# TS100C.net
KiCad netlist of a schematic drawn in Altium Designer
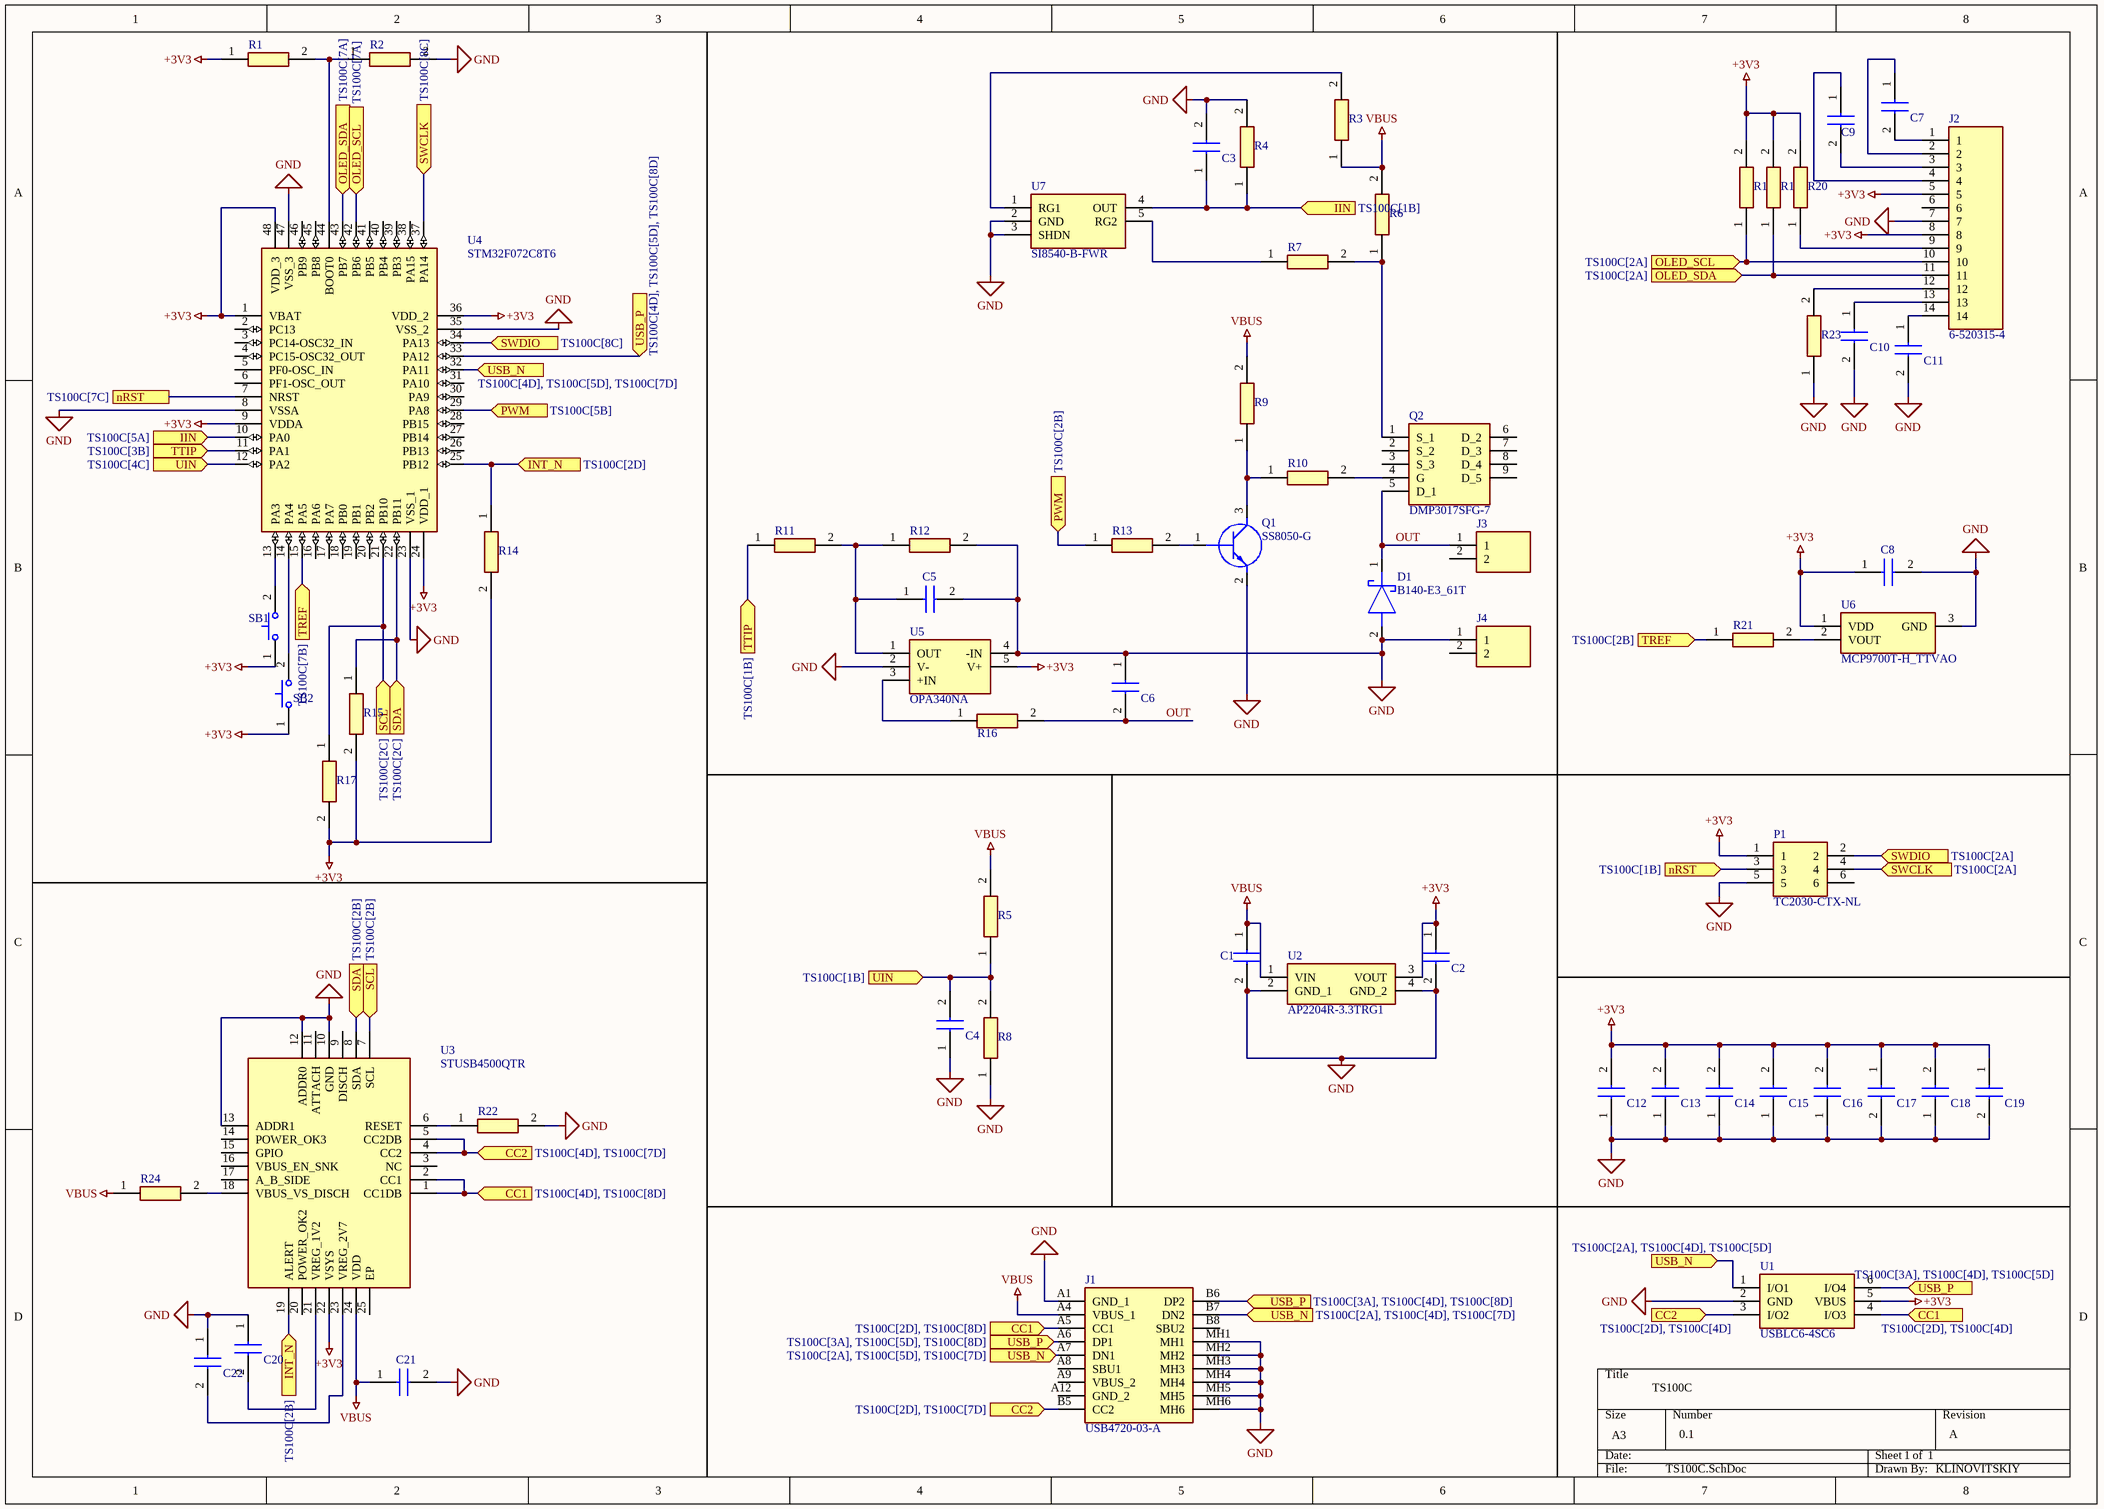
[diagram p0: TS100C.SchDoc]

(export (version "E")
  (design (tool "Eeschema 10.0.6"))
  (components
    (comp (ref "C1")
      (value "MAJCT168BB7105KTEA01")
      (footprint "SamacSys:MAJx16")
      (description "Capacitor")
      (libsource (lib "*") (part "MAJCT168BB7105KTEA01"))
    )
    (comp (ref "C2")
      (value "MAJCT168BB7105KTEA01")
      (footprint "SamacSys:MAJx16")
      (description "Capacitor")
      (libsource (lib "*") (part "MAJCT168BB7105KTEA01"))
    )
    (comp (ref "C3")
      (value "MAASU21GSB7104MTCA01")
      (footprint "SamacSys:CAPC2012X135N")
      (description "Capacitor")
      (fields (field (name "MOUSER PART NUMBER") "963-MAASU21GSB7104M"))
      (libsource (lib "*") (part "MAASU21GSB7104MTCA01"))
    )
    (comp (ref "C4")
      (value "MAASU21GSB7104MTCA01")
      (footprint "SamacSys:CAPC2012X135N")
      (description "Capacitor")
      (fields (field (name "MOUSER PART NUMBER") "963-MAASU21GSB7104M"))
      (libsource (lib "*") (part "MAASU21GSB7104MTCA01"))
    )
    (comp (ref "C5")
      (value "C0805C180JAGACTU")
      (footprint "SamacSys:C0805")
      (description "Capacitor")
      (fields (field (name "MOUSER PART NUMBER") "80-C0805C180JAGACTU"))
      (libsource (lib "*") (part "C0805C180JAGACTU"))
    )
    (comp (ref "C6")
      (value "C0805C180JAGACTU")
      (footprint "SamacSys:C0805")
      (description "Capacitor")
      (fields (field (name "MOUSER PART NUMBER") "80-C0805C180JAGACTU"))
      (libsource (lib "*") (part "C0805C180JAGACTU"))
    )
    (comp (ref "C7")
      (value "MAJCT168BB7105KTEA01")
      (footprint "SamacSys:MAJx16")
      (description "Capacitor")
      (libsource (lib "*") (part "MAJCT168BB7105KTEA01"))
    )
    (comp (ref "C8")
      (value "MAASU21GSB7104MTCA01")
      (footprint "SamacSys:CAPC2012X135N")
      (description "Capacitor")
      (fields (field (name "MOUSER PART NUMBER") "963-MAASU21GSB7104M"))
      (libsource (lib "*") (part "MAASU21GSB7104MTCA01"))
    )
    (comp (ref "C9")
      (value "MAJCT168BB7105KTEA01")
      (footprint "SamacSys:MAJx16")
      (description "Capacitor")
      (libsource (lib "*") (part "MAJCT168BB7105KTEA01"))
    )
    (comp (ref "C10")
      (value "MAJCT168BB7105KTEA01")
      (footprint "SamacSys:MAJx16")
      (description "Capacitor")
      (libsource (lib "*") (part "MAJCT168BB7105KTEA01"))
    )
    (comp (ref "C11")
      (value "MAJCT168BB7105KTEA01")
      (footprint "SamacSys:MAJx16")
      (description "Capacitor")
      (libsource (lib "*") (part "MAJCT168BB7105KTEA01"))
    )
    (comp (ref "C12")
      (value "MAASU21GSB7104MTCA01")
      (footprint "SamacSys:CAPC2012X135N")
      (description "Capacitor")
      (fields (field (name "MOUSER PART NUMBER") "963-MAASU21GSB7104M"))
      (libsource (lib "*") (part "MAASU21GSB7104MTCA01"))
    )
    (comp (ref "C13")
      (value "MAASU21GSB7104MTCA01")
      (footprint "SamacSys:CAPC2012X135N")
      (description "Capacitor")
      (fields (field (name "MOUSER PART NUMBER") "963-MAASU21GSB7104M"))
      (libsource (lib "*") (part "MAASU21GSB7104MTCA01"))
    )
    (comp (ref "C14")
      (value "MAASU21GSB7104MTCA01")
      (footprint "SamacSys:CAPC2012X135N")
      (description "Capacitor")
      (fields (field (name "MOUSER PART NUMBER") "963-MAASU21GSB7104M"))
      (libsource (lib "*") (part "MAASU21GSB7104MTCA01"))
    )
    (comp (ref "C15")
      (value "MAASU21GSB7104MTCA01")
      (footprint "SamacSys:CAPC2012X135N")
      (description "Capacitor")
      (fields (field (name "MOUSER PART NUMBER") "963-MAASU21GSB7104M"))
      (libsource (lib "*") (part "MAASU21GSB7104MTCA01"))
    )
    (comp (ref "C16")
      (value "MAASU21GSB7104MTCA01")
      (footprint "SamacSys:CAPC2012X135N")
      (description "Capacitor")
      (fields (field (name "MOUSER PART NUMBER") "963-MAASU21GSB7104M"))
      (libsource (lib "*") (part "MAASU21GSB7104MTCA01"))
    )
    (comp (ref "C17")
      (value "MAJCT168BB7105KTEA01")
      (footprint "SamacSys:MAJx16")
      (description "Capacitor")
      (libsource (lib "*") (part "MAJCT168BB7105KTEA01"))
    )
    (comp (ref "C18")
      (value "MAASU21GSB7104MTCA01")
      (footprint "SamacSys:CAPC2012X135N")
      (description "Capacitor")
      (fields (field (name "MOUSER PART NUMBER") "963-MAASU21GSB7104M"))
      (libsource (lib "*") (part "MAASU21GSB7104MTCA01"))
    )
    (comp (ref "C19")
      (value "MAJCT168BB7105KTEA01")
      (footprint "SamacSys:MAJx16")
      (description "Capacitor")
      (libsource (lib "*") (part "MAJCT168BB7105KTEA01"))
    )
    (comp (ref "C20")
      (value "MAJCT168BB7105KTEA01")
      (footprint "SamacSys:MAJx16")
      (description "Capacitor")
      (libsource (lib "*") (part "MAJCT168BB7105KTEA01"))
    )
    (comp (ref "C21")
      (value "MAASU21GSB7104MTCA01")
      (footprint "SamacSys:CAPC2012X135N")
      (description "Capacitor")
      (fields (field (name "MOUSER PART NUMBER") "963-MAASU21GSB7104M"))
      (libsource (lib "*") (part "MAASU21GSB7104MTCA01"))
    )
    (comp (ref "C22")
      (value "MAJCT168BB7105KTEA01")
      (footprint "SamacSys:MAJx16")
      (description "Capacitor")
      (libsource (lib "*") (part "MAJCT168BB7105KTEA01"))
    )
    (comp (ref "D1")
      (value "B140-E3_61T")
      (footprint "SamacSys:DIOM5127X229N")
      (description "Schottky Diode")
      (fields
        (field (name "MANUFACTURER_PART_NUMBER") "B140-E3/61T")
        (field (name "MOUSER PART NUMBER") "625-B140-E3/61T")
      )
      (libsource (lib "*") (part "B140-E3_61T"))
    )
    (comp (ref "J1")
      (value "USB4720-03-A")
      (footprint "SamacSys:USB472003A")
      (description "Connector")
      (fields (field (name "MOUSER PART NUMBER") "640-USB472003A"))
      (libsource (lib "*") (part "USB4720-03-A"))
    )
    (comp (ref "J2")
      (value "6-520315-4")
      (footprint "SamacSys:65203154")
      (description "Connector")
      (fields (field (name "MOUSER PART NUMBER") "571-6-520315-4"))
      (libsource (lib "*") (part "6-520315-4"))
    )
    (comp (ref "J3")
      (value "1-770166-0")
      (footprint "SamacSys:17701660")
      (description "Connector")
      (fields (field (name "MOUSER PART NUMBER") "571-1-770166-0"))
      (libsource (lib "*") (part "1-770166-0"))
    )
    (comp (ref "J4")
      (value "1-770166-0")
      (footprint "SamacSys:17701660")
      (description "Connector")
      (fields (field (name "MOUSER PART NUMBER") "571-1-770166-0"))
      (libsource (lib "*") (part "1-770166-0"))
    )
    (comp (ref "P1")
      (value "TC2030-CTX-NL")
      (footprint "SamacSys:TC2030MCPNL10")
      (description "Connector")
      (libsource (lib "*") (part "TC2030-CTX-NL"))
    )
    (comp (ref "Q1")
      (value "SS8050-G")
      (footprint "SamacSys:SOT95P240X115-3N")
      (description "Transistor BJT NPN")
      (fields (field (name "MOUSER PART NUMBER") "750-SS8050-G"))
      (libsource (lib "*") (part "SS8050-G"))
    )
    (comp (ref "Q2")
      (value "DMP3017SFG-7")
      (footprint "SamacSys:DMP3007SFG7")
      (description "MOSFET (P-Channel)")
      (fields (field (name "MOUSER PART NUMBER") "621-DMP3017SFG-7"))
      (libsource (lib "*") (part "DMP3017SFG-7"))
    )
    (comp (ref "R1")
      (value "WSL080500000ZEA9")
      (footprint "SamacSys:RESC2013X84N")
      (description "Resistor")
      (fields (field (name "MOUSER PART NUMBER") "71-WSL080500000ZEA9"))
      (libsource (lib "*") (part "WSL080500000ZEA9"))
    )
    (comp (ref "R2")
      (value "RN73C2A2K37BTG")
      (footprint "SamacSys:RESC2012X65N")
      (description "Resistor")
      (libsource (lib "") (part "RN73C2A2K37BTG_2"))
    )
    (comp (ref "R3")
      (value "SMQW133RJT")
      (footprint "SamacSys:RESM7940X385N")
      (description "Resistor")
      (libsource (lib "") (part "SMQW133RJT_1"))
    )
    (comp (ref "R4")
      (value "RN73C2A2K37BTG")
      (footprint "SamacSys:RESC2012X65N")
      (description "Resistor")
      (libsource (lib "*") (part "RN73C2A2K37BTG"))
    )
    (comp (ref "R5")
      (value "CRCW0805560KJNEAHP")
      (footprint "SamacSys:RESC2012X60N")
      (description "Resistor")
      (fields (field (name "MOUSER PART NUMBER") "71-CRCW0805560KJNEAH"))
      (libsource (lib "*") (part "CRCW0805560KJNEAHP"))
    )
    (comp (ref "R6")
      (value "WSLP0805R0100DEA")
      (footprint "SamacSys:RESC2013X58N")
      (description "Resistor")
      (fields (field (name "MOUSER PART NUMBER") "71-WSLP0805R0100DEA"))
      (libsource (lib "*") (part "WSLP0805R0100DEA"))
    )
    (comp (ref "R7")
      (value "SMQW133RJT")
      (footprint "SamacSys:RESM7940X385N")
      (description "Resistor")
      (libsource (lib "*") (part "SMQW133RJT"))
    )
    (comp (ref "R8")
      (value "SFR01MZPF1003")
      (footprint "SamacSys:RESC1005X40N")
      (description "Resistor")
      (fields (field (name "MOUSER PART NUMBER") "755-SFR01MZPF1003"))
      (libsource (lib "") (part "SFR01MZPF1003_1"))
    )
    (comp (ref "R9")
      (value "RN73C2A2K37BTG")
      (footprint "SamacSys:RESC2012X65N")
      (description "Resistor")
      (libsource (lib "*") (part "RN73C2A2K37BTG"))
    )
    (comp (ref "R10")
      (value "ERJ-UP6D20R0V")
      (footprint "SamacSys:ERJUP6")
      (description "Resistor")
      (libsource (lib "*") (part "ERJ-UP6D20R0V"))
    )
    (comp (ref "R11")
      (value "RN73C2A2K37BTG")
      (footprint "SamacSys:RESC2012X65N")
      (description "Resistor")
      (libsource (lib "") (part "RN73C2A2K37BTG_2"))
    )
    (comp (ref "R12")
      (value "RCV2010750KFKEFAT")
      (footprint "SamacSys:RESC5025X70N")
      (description "Resistor")
      (fields (field (name "MOUSER PART NUMBER") "71-RCV2010750KFKEFAT"))
      (libsource (lib "*") (part "RCV2010750KFKEFAT"))
    )
    (comp (ref "R13")
      (value "RN73C2A2K37BTG")
      (footprint "SamacSys:RESC2012X65N")
      (description "Resistor")
      (libsource (lib "") (part "RN73C2A2K37BTG_2"))
    )
    (comp (ref "R14")
      (value "RN73C2A2K37BTG")
      (footprint "SamacSys:RESC2012X65N")
      (description "Resistor")
      (libsource (lib "") (part "RN73C2A2K37BTG_1"))
    )
    (comp (ref "R15")
      (value "RN73C2A2K37BTG")
      (footprint "SamacSys:RESC2012X65N")
      (description "Resistor")
      (libsource (lib "") (part "RN73C2A2K37BTG_1"))
    )
    (comp (ref "R16")
      (value "SFR01MZPF1003")
      (footprint "SamacSys:RESC1005X40N")
      (description "Resistor")
      (fields (field (name "MOUSER PART NUMBER") "755-SFR01MZPF1003"))
      (libsource (lib "*") (part "SFR01MZPF1003"))
    )
    (comp (ref "R17")
      (value "RN73C2A2K37BTG")
      (footprint "SamacSys:RESC2012X65N")
      (description "Resistor")
      (libsource (lib "") (part "RN73C2A2K37BTG_1"))
    )
    (comp (ref "R18")
      (value "RN73C2A2K37BTG")
      (footprint "SamacSys:RESC2012X65N")
      (description "Resistor")
      (libsource (lib "*") (part "RN73C2A2K37BTG"))
    )
    (comp (ref "R19")
      (value "RN73C2A2K37BTG")
      (footprint "SamacSys:RESC2012X65N")
      (description "Resistor")
      (libsource (lib "*") (part "RN73C2A2K37BTG"))
    )
    (comp (ref "R20")
      (value "RN73C2A2K37BTG")
      (footprint "SamacSys:RESC2012X65N")
      (description "Resistor")
      (libsource (lib "*") (part "RN73C2A2K37BTG"))
    )
    (comp (ref "R21")
      (value "RN73C2A2K37BTG")
      (footprint "SamacSys:RESC2012X65N")
      (description "Resistor")
      (libsource (lib "") (part "RN73C2A2K37BTG_2"))
    )
    (comp (ref "R22")
      (value "RN73C2A2K37BTG")
      (footprint "SamacSys:RESC2012X65N")
      (description "Resistor")
      (libsource (lib "") (part "RN73C2A2K37BTG_2"))
    )
    (comp (ref "R23")
      (value "CRCW0805560KJNEAHP")
      (footprint "SamacSys:RESC2012X60N")
      (description "Resistor")
      (fields (field (name "MOUSER PART NUMBER") "71-CRCW0805560KJNEAH"))
      (libsource (lib "*") (part "CRCW0805560KJNEAHP"))
    )
    (comp (ref "R24")
      (value "RN73C2A2K37BTG")
      (footprint "SamacSys:RESC2012X65N")
      (description "Resistor")
      (libsource (lib "") (part "RN73C2A2K37BTG_2"))
    )
    (comp (ref "SB1")
      (value "8631CQD2")
      (footprint "SamacSys:8631CQD2")
      (description "Switch (2-Pin Push)")
      (fields (field (name "MOUSER PART NUMBER") "611-8631-261"))
      (libsource (lib "*") (part "8631CQD2"))
    )
    (comp (ref "SB2")
      (value "8631CQD2")
      (footprint "SamacSys:8631CQD2")
      (description "Switch (2-Pin Push)")
      (fields (field (name "MOUSER PART NUMBER") "611-8631-261"))
      (libsource (lib "*") (part "8631CQD2"))
    )
    (comp (ref "U1")
      (value "USBLC6-4SC6")
      (footprint "SamacSys:SOT95P280X145-6N")
      (description "Integrated Circuit")
      (fields (field (name "MOUSER PART NUMBER") "511-USBLC6-4SC6"))
      (libsource (lib "*") (part "USBLC6-4SC6"))
    )
    (comp (ref "U2")
      (value "AP2204R-3.3TRG1")
      (footprint "SamacSys:AP2204R33TRG1")
      (description "Integrated Circuit")
      (fields (field (name "MOUSER PART NUMBER") "621-AP2204R-3.3TRG1"))
      (libsource (lib "*") (part "AP2204R-3.3TRG1"))
    )
    (comp (ref "U3")
      (value "STUSB4500QTR")
      (footprint "SamacSys:QFN50P400X400X100-25N-D")
      (description "Integrated Circuit")
      (fields (field (name "MOUSER PART NUMBER") "511-STUSB4500QTR"))
      (libsource (lib "*") (part "STUSB4500QTR"))
    )
    (comp (ref "U4")
      (value "STM32F072C8T6")
      (footprint "SamacSys:QFP50P900X900X160-48N")
      (description "Integrated Circuit")
      (fields (field (name "MOUSER PART NUMBER") "511-STM32F072C8T6"))
      (libsource (lib "*") (part "STM32F072C8T6"))
    )
    (comp (ref "U5")
      (value "OPA340NA")
      (footprint "SamacSys:SOT95P280X145-5N")
      (description "Integrated Circuit")
      (libsource (lib "*") (part "OPA340NA"))
    )
    (comp (ref "U6")
      (value "MCP9700T-H_TTVAO")
      (footprint "SamacSys:SOT95P237X112-3N")
      (description "Integrated Circuit")
      (fields
        (field (name "MANUFACTURER_PART_NUMBER") "MCP9700T-H/TTVAO")
        (field (name "MOUSER PART NUMBER") "579-MCP9700T-H/TTVAO")
      )
      (libsource (lib "*") (part "MCP9700T-H_TTVAO"))
    )
    (comp (ref "U7")
      (value "SI8540-B-FWR")
      (footprint "SamacSys:SOT95P280X145-5N")
      (description "Integrated Circuit")
      (fields (field (name "MOUSER PART NUMBER") "634-SI8540-B-FWR"))
      (libsource (lib "*") (part "SI8540-B-FWR"))
    )
  )
  (nets
    (net (code "1") (name "+3V3") (class "Default")
      (node (ref "C12") (pin "2") (pinfunction "2_2") (pintype "passive"))
      (node (ref "C13") (pin "2") (pinfunction "2_2") (pintype "passive"))
      (node (ref "C14") (pin "2") (pinfunction "2_2") (pintype "passive"))
      (node (ref "C15") (pin "2") (pinfunction "2_2") (pintype "passive"))
      (node (ref "C16") (pin "2") (pinfunction "2_2") (pintype "passive"))
      (node (ref "C17") (pin "1") (pinfunction "1_1") (pintype "passive"))
      (node (ref "C18") (pin "2") (pinfunction "2_2") (pintype "passive"))
      (node (ref "C19") (pin "1") (pinfunction "1_1") (pintype "passive"))
      (node (ref "C2") (pin "1") (pinfunction "1_1") (pintype "passive"))
      (node (ref "C8") (pin "1") (pinfunction "1_1") (pintype "passive"))
      (node (ref "J2") (pin "5") (pinfunction "5_5") (pintype "passive"))
      (node (ref "J2") (pin "8") (pinfunction "8_8") (pintype "passive"))
      (node (ref "P1") (pin "1") (pinfunction "1_1") (pintype "passive"))
      (node (ref "R1") (pin "1") (pinfunction "1_1") (pintype "passive"))
      (node (ref "R14") (pin "2") (pinfunction "2_2") (pintype "passive"))
      (node (ref "R15") (pin "2") (pinfunction "2_2") (pintype "passive"))
      (node (ref "R17") (pin "2") (pinfunction "2_2") (pintype "passive"))
      (node (ref "R18") (pin "2") (pinfunction "2_2") (pintype "passive"))
      (node (ref "R19") (pin "2") (pinfunction "2_2") (pintype "passive"))
      (node (ref "R20") (pin "2") (pinfunction "2_2") (pintype "passive"))
      (node (ref "SB1") (pin "1") (pinfunction "N.O._1_1") (pintype "passive"))
      (node (ref "SB2") (pin "1") (pinfunction "N.O._1_1") (pintype "passive"))
      (node (ref "U1") (pin "5") (pinfunction "VBUS_5") (pintype "passive"))
      (node (ref "U2") (pin "3") (pinfunction "VOUT_3") (pintype "passive"))
      (node (ref "U3") (pin "22") (pinfunction "VSYS_22") (pintype "passive"))
      (node (ref "U4") (pin "1") (pinfunction "VBAT_1") (pintype "power_in"))
      (node (ref "U4") (pin "24") (pinfunction "VDD_1_24") (pintype "power_in"))
      (node (ref "U4") (pin "36") (pinfunction "VDD_2_36") (pintype "power_in"))
      (node (ref "U4") (pin "48") (pinfunction "VDD_3_48") (pintype "power_in"))
      (node (ref "U4") (pin "9") (pinfunction "VDDA_9") (pintype "power_in"))
      (node (ref "U5") (pin "5") (pinfunction "V+_5") (pintype "passive"))
      (node (ref "U6") (pin "1") (pinfunction "VDD_1") (pintype "passive"))
    )
    (net (code "2") (name "/CC1") (class "Default")
      (node (ref "J1") (pin "A5") (pinfunction "CC1_A5") (pintype "passive"))
      (node (ref "U1") (pin "4") (pinfunction "I/O3_4") (pintype "passive"))
      (node (ref "U3") (pin "1") (pinfunction "CC1DB_1") (pintype "passive"))
      (node (ref "U3") (pin "2") (pinfunction "CC1_2") (pintype "passive"))
    )
    (net (code "3") (name "/CC2") (class "Default")
      (node (ref "J1") (pin "B5") (pinfunction "CC2_B5") (pintype "passive"))
      (node (ref "U1") (pin "3") (pinfunction "I/O2_3") (pintype "passive"))
      (node (ref "U3") (pin "4") (pinfunction "CC2_4") (pintype "passive"))
      (node (ref "U3") (pin "5") (pinfunction "CC2DB_5") (pintype "passive"))
    )
    (net (code "4") (name "/IIN") (class "Default")
      (node (ref "C3") (pin "1") (pinfunction "1_1") (pintype "passive"))
      (node (ref "R4") (pin "1") (pinfunction "1_1") (pintype "passive"))
      (node (ref "U4") (pin "10") (pinfunction "PA0_10") (pintype "bidirectional"))
      (node (ref "U7") (pin "4") (pinfunction "OUT_4") (pintype "passive"))
    )
    (net (code "5") (name "/INT_N") (class "Default")
      (node (ref "R14") (pin "1") (pinfunction "1_1") (pintype "passive"))
      (node (ref "U3") (pin "19") (pinfunction "ALERT_19") (pintype "passive"))
      (node (ref "U4") (pin "25") (pinfunction "PB12_25") (pintype "bidirectional"))
    )
    (net (code "6") (name "/OLED_SCL") (class "Default")
      (node (ref "J2") (pin "10") (pinfunction "10_10") (pintype "passive"))
      (node (ref "R18") (pin "1") (pinfunction "1_1") (pintype "passive"))
      (node (ref "U4") (pin "42") (pinfunction "PB6_42") (pintype "bidirectional"))
    )
    (net (code "7") (name "/OLED_SDA") (class "Default")
      (node (ref "J2") (pin "11") (pinfunction "11_11") (pintype "passive"))
      (node (ref "R19") (pin "1") (pinfunction "1_1") (pintype "passive"))
      (node (ref "U4") (pin "43") (pinfunction "PB7_43") (pintype "bidirectional"))
    )
    (net (code "8") (name "/OUT") (class "Default")
      (node (ref "C6") (pin "2") (pinfunction "2_2") (pintype "passive"))
      (node (ref "D1") (pin "1") (pinfunction "K_1") (pintype "passive"))
      (node (ref "J3") (pin "1") (pinfunction "1_1") (pintype "passive"))
      (node (ref "Q2") (pin "5") (pinfunction "D_1_5") (pintype "passive"))
      (node (ref "R16") (pin "2") (pinfunction "2_2") (pintype "passive"))
    )
    (net (code "9") (name "/PWM") (class "Default")
      (node (ref "R13") (pin "1") (pinfunction "1_1") (pintype "passive"))
      (node (ref "U4") (pin "29") (pinfunction "PA8_29") (pintype "bidirectional"))
    )
    (net (code "10") (name "/SCL") (class "Default")
      (node (ref "R17") (pin "1") (pinfunction "1_1") (pintype "passive"))
      (node (ref "U3") (pin "7") (pinfunction "SCL_7") (pintype "passive"))
      (node (ref "U4") (pin "21") (pinfunction "PB10_21") (pintype "bidirectional"))
    )
    (net (code "11") (name "/SDA") (class "Default")
      (node (ref "R15") (pin "1") (pinfunction "1_1") (pintype "passive"))
      (node (ref "U3") (pin "8") (pinfunction "SDA_8") (pintype "passive"))
      (node (ref "U4") (pin "22") (pinfunction "PB11_22") (pintype "bidirectional"))
    )
    (net (code "12") (name "/SWCLK") (class "Default")
      (node (ref "P1") (pin "4") (pinfunction "4_4") (pintype "passive"))
      (node (ref "U4") (pin "37") (pinfunction "PA14_37") (pintype "bidirectional"))
    )
    (net (code "13") (name "/SWDIO") (class "Default")
      (node (ref "P1") (pin "2") (pinfunction "2_2") (pintype "passive"))
      (node (ref "U4") (pin "34") (pinfunction "PA13_34") (pintype "bidirectional"))
    )
    (net (code "14") (name "/TREF") (class "Default")
      (node (ref "R21") (pin "1") (pinfunction "1_1") (pintype "passive"))
      (node (ref "U4") (pin "15") (pinfunction "PA5_15") (pintype "bidirectional"))
    )
    (net (code "15") (name "/TTIP") (class "Default")
      (node (ref "R11") (pin "1") (pinfunction "1_1") (pintype "passive"))
      (node (ref "U4") (pin "11") (pinfunction "PA1_11") (pintype "bidirectional"))
    )
    (net (code "16") (name "/UIN") (class "Default")
      (node (ref "C4") (pin "2") (pinfunction "2_2") (pintype "passive"))
      (node (ref "R5") (pin "1") (pinfunction "1_1") (pintype "passive"))
      (node (ref "R8") (pin "2") (pinfunction "2_2") (pintype "passive"))
      (node (ref "U4") (pin "12") (pinfunction "PA2_12") (pintype "bidirectional"))
    )
    (net (code "17") (name "/USB_N") (class "Default")
      (node (ref "J1") (pin "A7") (pinfunction "DN1_A7") (pintype "passive"))
      (node (ref "J1") (pin "B7") (pinfunction "DN2_B7") (pintype "passive"))
      (node (ref "U1") (pin "1") (pinfunction "I/O1_1") (pintype "passive"))
      (node (ref "U4") (pin "32") (pinfunction "PA11_32") (pintype "bidirectional"))
    )
    (net (code "18") (name "/USB_P") (class "Default")
      (node (ref "J1") (pin "A6") (pinfunction "DP1_A6") (pintype "passive"))
      (node (ref "J1") (pin "B6") (pinfunction "DP2_B6") (pintype "passive"))
      (node (ref "U1") (pin "6") (pinfunction "I/O4_6") (pintype "passive"))
      (node (ref "U4") (pin "33") (pinfunction "PA12_33") (pintype "bidirectional"))
    )
    (net (code "19") (name "/nRST") (class "Default")
      (node (ref "P1") (pin "3") (pinfunction "3_3") (pintype "passive"))
      (node (ref "U4") (pin "7") (pinfunction "NRST_7") (pintype "passive"))
    )
    (net (code "20") (name "GND") (class "Default")
      (node (ref "C1") (pin "2") (pinfunction "2_2") (pintype "passive"))
      (node (ref "C10") (pin "2") (pinfunction "2_2") (pintype "passive"))
      (node (ref "C11") (pin "2") (pinfunction "2_2") (pintype "passive"))
      (node (ref "C12") (pin "1") (pinfunction "1_1") (pintype "passive"))
      (node (ref "C13") (pin "1") (pinfunction "1_1") (pintype "passive"))
      (node (ref "C14") (pin "1") (pinfunction "1_1") (pintype "passive"))
      (node (ref "C15") (pin "1") (pinfunction "1_1") (pintype "passive"))
      (node (ref "C16") (pin "1") (pinfunction "1_1") (pintype "passive"))
      (node (ref "C17") (pin "2") (pinfunction "2_2") (pintype "passive"))
      (node (ref "C18") (pin "1") (pinfunction "1_1") (pintype "passive"))
      (node (ref "C19") (pin "2") (pinfunction "2_2") (pintype "passive"))
      (node (ref "C2") (pin "2") (pinfunction "2_2") (pintype "passive"))
      (node (ref "C20") (pin "1") (pinfunction "1_1") (pintype "passive"))
      (node (ref "C21") (pin "2") (pinfunction "2_2") (pintype "passive"))
      (node (ref "C22") (pin "1") (pinfunction "1_1") (pintype "passive"))
      (node (ref "C3") (pin "2") (pinfunction "2_2") (pintype "passive"))
      (node (ref "C4") (pin "1") (pinfunction "1_1") (pintype "passive"))
      (node (ref "C5") (pin "2") (pinfunction "2_2") (pintype "passive"))
      (node (ref "C6") (pin "1") (pinfunction "1_1") (pintype "passive"))
      (node (ref "C8") (pin "2") (pinfunction "2_2") (pintype "passive"))
      (node (ref "D1") (pin "2") (pinfunction "A_2") (pintype "passive"))
      (node (ref "J1") (pin "A1") (pinfunction "GND_1_A1") (pintype "passive"))
      (node (ref "J1") (pin "MH1") (pinfunction "MH1_MH1") (pintype "passive"))
      (node (ref "J1") (pin "MH2") (pinfunction "MH2_MH2") (pintype "passive"))
      (node (ref "J1") (pin "MH3") (pinfunction "MH3_MH3") (pintype "passive"))
      (node (ref "J1") (pin "MH4") (pinfunction "MH4_MH4") (pintype "passive"))
      (node (ref "J1") (pin "MH5") (pinfunction "MH5_MH5") (pintype "passive"))
      (node (ref "J1") (pin "MH6") (pinfunction "MH6_MH6") (pintype "passive"))
      (node (ref "J2") (pin "7") (pinfunction "7_7") (pintype "passive"))
      (node (ref "J4") (pin "1") (pinfunction "1_1") (pintype "passive"))
      (node (ref "P1") (pin "5") (pinfunction "5_5") (pintype "passive"))
      (node (ref "Q1") (pin "2") (pinfunction "E_2") (pintype "passive"))
      (node (ref "R12") (pin "2") (pinfunction "2_2") (pintype "passive"))
      (node (ref "R2") (pin "2") (pinfunction "2_2") (pintype "passive"))
      (node (ref "R22") (pin "2") (pinfunction "2_2") (pintype "passive"))
      (node (ref "R23") (pin "1") (pinfunction "1_1") (pintype "passive"))
      (node (ref "R4") (pin "2") (pinfunction "2_2") (pintype "passive"))
      (node (ref "R8") (pin "1") (pinfunction "1_1") (pintype "passive"))
      (node (ref "U1") (pin "2") (pinfunction "GND_2") (pintype "passive"))
      (node (ref "U2") (pin "2") (pinfunction "GND_1_2") (pintype "passive"))
      (node (ref "U2") (pin "4") (pinfunction "GND_2_4") (pintype "passive"))
      (node (ref "U3") (pin "10") (pinfunction "GND_10") (pintype "passive"))
      (node (ref "U3") (pin "12") (pinfunction "ADDR0_12") (pintype "passive"))
      (node (ref "U3") (pin "13") (pinfunction "ADDR1_13") (pintype "passive"))
      (node (ref "U4") (pin "23") (pinfunction "VSS_1_23") (pintype "power_in"))
      (node (ref "U4") (pin "35") (pinfunction "VSS_2_35") (pintype "power_in"))
      (node (ref "U4") (pin "47") (pinfunction "VSS_3_47") (pintype "power_in"))
      (node (ref "U4") (pin "8") (pinfunction "VSSA_8") (pintype "power_in"))
      (node (ref "U5") (pin "2") (pinfunction "V-_2") (pintype "passive"))
      (node (ref "U5") (pin "4") (pinfunction "-IN_4") (pintype "passive"))
      (node (ref "U6") (pin "3") (pinfunction "GND_3") (pintype "passive"))
      (node (ref "U7") (pin "2") (pinfunction "GND_2") (pintype "passive"))
      (node (ref "U7") (pin "3") (pinfunction "SHDN_3") (pintype "passive"))
    )
    (net (code "21") (name "Net-(C7-Pad1)") (class "Default")
      (node (ref "C7") (pin "1") (pinfunction "1_1") (pintype "passive"))
      (node (ref "J2") (pin "2") (pinfunction "2_2") (pintype "passive"))
    )
    (net (code "22") (name "Net-(C7-Pad2)") (class "Default")
      (node (ref "C7") (pin "2") (pinfunction "2_2") (pintype "passive"))
      (node (ref "J2") (pin "1") (pinfunction "1_1") (pintype "passive"))
    )
    (net (code "23") (name "Net-(C9-Pad1)") (class "Default")
      (node (ref "C9") (pin "1") (pinfunction "1_1") (pintype "passive"))
      (node (ref "J2") (pin "4") (pinfunction "4_4") (pintype "passive"))
    )
    (net (code "24") (name "Net-(C9-Pad2)") (class "Default")
      (node (ref "C9") (pin "2") (pinfunction "2_2") (pintype "passive"))
      (node (ref "J2") (pin "3") (pinfunction "3_3") (pintype "passive"))
    )
    (net (code "25") (name "Net-(C10-Pad1)") (class "Default")
      (node (ref "C10") (pin "1") (pinfunction "1_1") (pintype "passive"))
      (node (ref "J2") (pin "13") (pinfunction "13_13") (pintype "passive"))
    )
    (net (code "26") (name "Net-(C11-Pad1)") (class "Default")
      (node (ref "C11") (pin "1") (pinfunction "1_1") (pintype "passive"))
      (node (ref "J2") (pin "14") (pinfunction "14_14") (pintype "passive"))
    )
    (net (code "27") (name "Net-(J2-Pad9)") (class "Default")
      (node (ref "J2") (pin "9") (pinfunction "9_9") (pintype "passive"))
      (node (ref "R20") (pin "1") (pinfunction "1_1") (pintype "passive"))
    )
    (net (code "28") (name "Net-(J2-Pad12)") (class "Default")
      (node (ref "J2") (pin "12") (pinfunction "12_12") (pintype "passive"))
      (node (ref "R23") (pin "2") (pinfunction "2_2") (pintype "passive"))
    )
    (net (code "29") (name "Net-(Q1-B)") (class "Default")
      (node (ref "Q1") (pin "1") (pinfunction "B_1") (pintype "passive"))
      (node (ref "R13") (pin "2") (pinfunction "2_2") (pintype "passive"))
    )
    (net (code "30") (name "Net-(Q1-C)") (class "Default")
      (node (ref "Q1") (pin "3") (pinfunction "C_3") (pintype "passive"))
      (node (ref "R10") (pin "1") (pinfunction "1_1") (pintype "passive"))
      (node (ref "R9") (pin "1") (pinfunction "1_1") (pintype "passive"))
    )
    (net (code "31") (name "Net-(Q2-G)") (class "Default")
      (node (ref "Q2") (pin "4") (pinfunction "G_4") (pintype "passive"))
      (node (ref "R10") (pin "2") (pinfunction "2_2") (pintype "passive"))
    )
    (net (code "32") (name "Net-(Q2-S_1)") (class "Default")
      (node (ref "Q2") (pin "1") (pinfunction "S_1_1") (pintype "passive"))
      (node (ref "R6") (pin "1") (pinfunction "1_1") (pintype "passive"))
      (node (ref "R7") (pin "2") (pinfunction "2_2") (pintype "passive"))
    )
    (net (code "33") (name "Net-(SB1-N.O._2)") (class "Default")
      (node (ref "SB1") (pin "2") (pinfunction "N.O._2_2") (pintype "passive"))
      (node (ref "U4") (pin "13") (pinfunction "PA3_13") (pintype "bidirectional"))
    )
    (net (code "34") (name "Net-(SB2-N.O._2)") (class "Default")
      (node (ref "SB2") (pin "2") (pinfunction "N.O._2_2") (pintype "passive"))
      (node (ref "U4") (pin "14") (pinfunction "PA4_14") (pintype "bidirectional"))
    )
    (net (code "35") (name "Net-(U3-RESET)") (class "Default")
      (node (ref "R22") (pin "1") (pinfunction "1_1") (pintype "passive"))
      (node (ref "U3") (pin "6") (pinfunction "RESET_6") (pintype "passive"))
    )
    (net (code "36") (name "Net-(U3-VBUS_VS_DISCH)") (class "Default")
      (node (ref "R24") (pin "2") (pinfunction "2_2") (pintype "passive"))
      (node (ref "U3") (pin "18") (pinfunction "VBUS_VS_DISCH_18") (pintype "passive"))
    )
    (net (code "37") (name "Net-(U3-VREG_1V2)") (class "Default")
      (node (ref "C20") (pin "2") (pinfunction "2_2") (pintype "passive"))
      (node (ref "U3") (pin "21") (pinfunction "VREG_1V2_21") (pintype "passive"))
    )
    (net (code "38") (name "Net-(U3-VREG_2V7)") (class "Default")
      (node (ref "C22") (pin "2") (pinfunction "2_2") (pintype "passive"))
      (node (ref "U3") (pin "23") (pinfunction "VREG_2V7_23") (pintype "passive"))
    )
    (net (code "39") (name "Net-(U4-BOOT0)") (class "Default")
      (node (ref "R1") (pin "2") (pinfunction "2_2") (pintype "passive"))
      (node (ref "R2") (pin "1") (pinfunction "1_1") (pintype "passive"))
      (node (ref "U4") (pin "44") (pinfunction "BOOT0_44") (pintype "passive"))
    )
    (net (code "40") (name "Net-(U5-+IN)") (class "Default")
      (node (ref "R16") (pin "1") (pinfunction "1_1") (pintype "passive"))
      (node (ref "U5") (pin "3") (pinfunction "+IN_3") (pintype "passive"))
    )
    (net (code "41") (name "Net-(U5-OUT)") (class "Default")
      (node (ref "C5") (pin "1") (pinfunction "1_1") (pintype "passive"))
      (node (ref "R11") (pin "2") (pinfunction "2_2") (pintype "passive"))
      (node (ref "R12") (pin "1") (pinfunction "1_1") (pintype "passive"))
      (node (ref "U5") (pin "1") (pinfunction "OUT_1") (pintype "passive"))
    )
    (net (code "42") (name "Net-(U6-VOUT)") (class "Default")
      (node (ref "R21") (pin "2") (pinfunction "2_2") (pintype "passive"))
      (node (ref "U6") (pin "2") (pinfunction "VOUT_2") (pintype "passive"))
    )
    (net (code "43") (name "Net-(U7-RG1)") (class "Default")
      (node (ref "R3") (pin "2") (pinfunction "2_2") (pintype "passive"))
      (node (ref "U7") (pin "1") (pinfunction "RG1_1") (pintype "passive"))
    )
    (net (code "44") (name "Net-(U7-RG2)") (class "Default")
      (node (ref "R7") (pin "1") (pinfunction "1_1") (pintype "passive"))
      (node (ref "U7") (pin "5") (pinfunction "RG2_5") (pintype "passive"))
    )
    (net (code "45") (name "VBUS") (class "Default")
      (node (ref "C1") (pin "1") (pinfunction "1_1") (pintype "passive"))
      (node (ref "C21") (pin "1") (pinfunction "1_1") (pintype "passive"))
      (node (ref "J1") (pin "A4") (pinfunction "VBUS_1_A4") (pintype "passive"))
      (node (ref "R24") (pin "1") (pinfunction "1_1") (pintype "passive"))
      (node (ref "R3") (pin "1") (pinfunction "1_1") (pintype "passive"))
      (node (ref "R5") (pin "2") (pinfunction "2_2") (pintype "passive"))
      (node (ref "R6") (pin "2") (pinfunction "2_2") (pintype "passive"))
      (node (ref "R9") (pin "2") (pinfunction "2_2") (pintype "passive"))
      (node (ref "U2") (pin "1") (pinfunction "VIN_1") (pintype "passive"))
      (node (ref "U3") (pin "24") (pinfunction "VDD_24") (pintype "passive"))
    )
    (net (code "46") (name "unconnected-(J1-GND_2-PadA12)") (class "Default")
      (node (ref "J1") (pin "A12") (pinfunction "GND_2_A12") (pintype "passive"))
    )
    (net (code "47") (name "unconnected-(J1-SBU1-PadA8)") (class "Default")
      (node (ref "J1") (pin "A8") (pinfunction "SBU1_A8") (pintype "passive"))
    )
    (net (code "48") (name "unconnected-(J1-SBU2-PadB8)") (class "Default")
      (node (ref "J1") (pin "B8") (pinfunction "SBU2_B8") (pintype "passive"))
    )
    (net (code "49") (name "unconnected-(J1-VBUS_2-PadA9)") (class "Default")
      (node (ref "J1") (pin "A9") (pinfunction "VBUS_2_A9") (pintype "passive"))
    )
    (net (code "50") (name "unconnected-(J2-Pad6)") (class "Default")
      (node (ref "J2") (pin "6") (pinfunction "6_6") (pintype "passive"))
    )
    (net (code "51") (name "unconnected-(J3-Pad2)") (class "Default")
      (node (ref "J3") (pin "2") (pinfunction "2_2") (pintype "passive"))
    )
    (net (code "52") (name "unconnected-(J4-Pad2)") (class "Default")
      (node (ref "J4") (pin "2") (pinfunction "2_2") (pintype "passive"))
    )
    (net (code "53") (name "unconnected-(P1-Pad6)") (class "Default")
      (node (ref "P1") (pin "6") (pinfunction "6_6") (pintype "passive"))
    )
    (net (code "54") (name "unconnected-(Q2-D_2-Pad6)") (class "Default")
      (node (ref "Q2") (pin "6") (pinfunction "D_2_6") (pintype "passive"))
    )
    (net (code "55") (name "unconnected-(Q2-D_3-Pad7)") (class "Default")
      (node (ref "Q2") (pin "7") (pinfunction "D_3_7") (pintype "passive"))
    )
    (net (code "56") (name "unconnected-(Q2-D_4-Pad8)") (class "Default")
      (node (ref "Q2") (pin "8") (pinfunction "D_4_8") (pintype "passive"))
    )
    (net (code "57") (name "unconnected-(Q2-D_5-Pad9)") (class "Default")
      (node (ref "Q2") (pin "9") (pinfunction "D_5_9") (pintype "passive"))
    )
    (net (code "58") (name "unconnected-(Q2-S_2-Pad2)") (class "Default")
      (node (ref "Q2") (pin "2") (pinfunction "S_2_2") (pintype "passive"))
    )
    (net (code "59") (name "unconnected-(Q2-S_3-Pad3)") (class "Default")
      (node (ref "Q2") (pin "3") (pinfunction "S_3_3") (pintype "passive"))
    )
    (net (code "60") (name "unconnected-(U3-ATTACH-Pad11)") (class "Default")
      (node (ref "U3") (pin "11") (pinfunction "ATTACH_11") (pintype "passive"))
    )
    (net (code "61") (name "unconnected-(U3-A_B_SIDE-Pad17)") (class "Default")
      (node (ref "U3") (pin "17") (pinfunction "A_B_SIDE_17") (pintype "passive"))
    )
    (net (code "62") (name "unconnected-(U3-DISCH-Pad9)") (class "Default")
      (node (ref "U3") (pin "9") (pinfunction "DISCH_9") (pintype "passive"))
    )
    (net (code "63") (name "unconnected-(U3-EP-Pad25)") (class "Default")
      (node (ref "U3") (pin "25") (pinfunction "EP_25") (pintype "passive"))
    )
    (net (code "64") (name "unconnected-(U3-GPIO-Pad15)") (class "Default")
      (node (ref "U3") (pin "15") (pinfunction "GPIO_15") (pintype "passive"))
    )
    (net (code "65") (name "unconnected-(U3-NC-Pad3)") (class "Default")
      (node (ref "U3") (pin "3") (pinfunction "NC_3") (pintype "passive"))
    )
    (net (code "66") (name "unconnected-(U3-POWER_OK2-Pad20)") (class "Default")
      (node (ref "U3") (pin "20") (pinfunction "POWER_OK2_20") (pintype "passive"))
    )
    (net (code "67") (name "unconnected-(U3-POWER_OK3-Pad14)") (class "Default")
      (node (ref "U3") (pin "14") (pinfunction "POWER_OK3_14") (pintype "passive"))
    )
    (net (code "68") (name "unconnected-(U3-VBUS_EN_SNK-Pad16)") (class "Default")
      (node (ref "U3") (pin "16") (pinfunction "VBUS_EN_SNK_16") (pintype "passive"))
    )
    (net (code "69") (name "unconnected-(U4-PA6-Pad16)") (class "Default")
      (node (ref "U4") (pin "16") (pinfunction "PA6_16") (pintype "bidirectional"))
    )
    (net (code "70") (name "unconnected-(U4-PA7-Pad17)") (class "Default")
      (node (ref "U4") (pin "17") (pinfunction "PA7_17") (pintype "bidirectional"))
    )
    (net (code "71") (name "unconnected-(U4-PA9-Pad30)") (class "Default")
      (node (ref "U4") (pin "30") (pinfunction "PA9_30") (pintype "bidirectional"))
    )
    (net (code "72") (name "unconnected-(U4-PA10-Pad31)") (class "Default")
      (node (ref "U4") (pin "31") (pinfunction "PA10_31") (pintype "bidirectional"))
    )
    (net (code "73") (name "unconnected-(U4-PA15-Pad38)") (class "Default")
      (node (ref "U4") (pin "38") (pinfunction "PA15_38") (pintype "bidirectional"))
    )
    (net (code "74") (name "unconnected-(U4-PB0-Pad18)") (class "Default")
      (node (ref "U4") (pin "18") (pinfunction "PB0_18") (pintype "bidirectional"))
    )
    (net (code "75") (name "unconnected-(U4-PB1-Pad19)") (class "Default")
      (node (ref "U4") (pin "19") (pinfunction "PB1_19") (pintype "bidirectional"))
    )
    (net (code "76") (name "unconnected-(U4-PB2-Pad20)") (class "Default")
      (node (ref "U4") (pin "20") (pinfunction "PB2_20") (pintype "bidirectional"))
    )
    (net (code "77") (name "unconnected-(U4-PB3-Pad39)") (class "Default")
      (node (ref "U4") (pin "39") (pinfunction "PB3_39") (pintype "bidirectional"))
    )
    (net (code "78") (name "unconnected-(U4-PB4-Pad40)") (class "Default")
      (node (ref "U4") (pin "40") (pinfunction "PB4_40") (pintype "bidirectional"))
    )
    (net (code "79") (name "unconnected-(U4-PB5-Pad41)") (class "Default")
      (node (ref "U4") (pin "41") (pinfunction "PB5_41") (pintype "bidirectional"))
    )
    (net (code "80") (name "unconnected-(U4-PB8-Pad45)") (class "Default")
      (node (ref "U4") (pin "45") (pinfunction "PB8_45") (pintype "bidirectional"))
    )
    (net (code "81") (name "unconnected-(U4-PB9-Pad46)") (class "Default")
      (node (ref "U4") (pin "46") (pinfunction "PB9_46") (pintype "bidirectional"))
    )
    (net (code "82") (name "unconnected-(U4-PB13-Pad26)") (class "Default")
      (node (ref "U4") (pin "26") (pinfunction "PB13_26") (pintype "bidirectional"))
    )
    (net (code "83") (name "unconnected-(U4-PB14-Pad27)") (class "Default")
      (node (ref "U4") (pin "27") (pinfunction "PB14_27") (pintype "bidirectional"))
    )
    (net (code "84") (name "unconnected-(U4-PB15-Pad28)") (class "Default")
      (node (ref "U4") (pin "28") (pinfunction "PB15_28") (pintype "bidirectional"))
    )
    (net (code "85") (name "unconnected-(U4-PC13-Pad2)") (class "Default")
      (node (ref "U4") (pin "2") (pinfunction "PC13_2") (pintype "bidirectional"))
    )
    (net (code "86") (name "unconnected-(U4-PC14-OSC32_IN-Pad3)") (class "Default")
      (node (ref "U4") (pin "3") (pinfunction "PC14-OSC32_IN_3") (pintype "bidirectional"))
    )
    (net (code "87") (name "unconnected-(U4-PC15-OSC32_OUT-Pad4)") (class "Default")
      (node (ref "U4") (pin "4") (pinfunction "PC15-OSC32_OUT_4") (pintype "bidirectional"))
    )
    (net (code "88") (name "unconnected-(U4-PF0-OSC_IN-Pad5)") (class "Default")
      (node (ref "U4") (pin "5") (pinfunction "PF0-OSC_IN_5") (pintype "passive"))
    )
    (net (code "89") (name "unconnected-(U4-PF1-OSC_OUT-Pad6)") (class "Default")
      (node (ref "U4") (pin "6") (pinfunction "PF1-OSC_OUT_6") (pintype "passive"))
    )
  )
)
